# oled_iic.net
KiCad netlist of a schematic drawn in Altium Designer
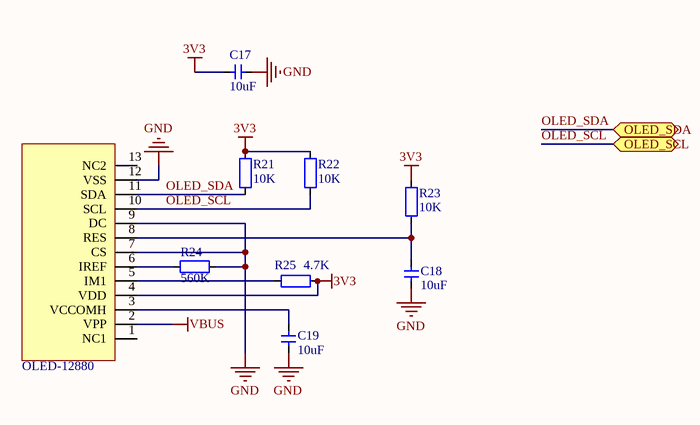
[diagram p0: oled_iic.SchDoc]

(export (version "E")
  (design (tool "Eeschema 10.0.6"))
  (components
    (comp (ref "1")
      (value "OLED-12880")
      (footprint "OLED-12880")
      (libsource (lib "mLib") (part "OLED-12880"))
    )
    (comp (ref "C17")
      (value "10uF")
      (footprint "CAP_0402")
      (description "Capacitor")
      (libsource (lib "MyPcbLib") (part "电容-0402"))
    )
    (comp (ref "C18")
      (value "10uF")
      (footprint "CAP_0402")
      (description "Capacitor")
      (libsource (lib "MyPcbLib") (part "电容-0402"))
    )
    (comp (ref "C19")
      (value "10uF")
      (footprint "CAP_0402")
      (description "Capacitor")
      (libsource (lib "MyPcbLib") (part "电容-0402"))
    )
    (comp (ref "R21")
      (value "10K")
      (footprint "RES_0402")
      (description "Resistor")
      (libsource (lib "") (part "电阻-0402_1"))
    )
    (comp (ref "R22")
      (value "10K")
      (footprint "RES_0402")
      (description "Resistor")
      (libsource (lib "") (part "电阻-0402_1"))
    )
    (comp (ref "R23")
      (value "10K")
      (footprint "RES_0402")
      (description "Resistor")
      (libsource (lib "") (part "电阻-0402_1"))
    )
    (comp (ref "R24")
      (value "560K")
      (footprint "RES_0402")
      (description "Resistor")
      (libsource (lib "MyPcbLib") (part "电阻-0402"))
    )
    (comp (ref "R25")
      (value "4.7K")
      (footprint "RES_0402")
      (description "Resistor")
      (libsource (lib "MyPcbLib") (part "电阻-0402"))
    )
  )
  (nets
    (net (code "1") (name "/OLED_SCL") (class "Default")
      (node (ref "1") (pin "10") (pinfunction "SCL_10") (pintype "passive"))
      (node (ref "R22") (pin "1") (pinfunction "1_1") (pintype "passive"))
    )
    (net (code "2") (name "/OLED_SDA") (class "Default")
      (node (ref "1") (pin "11") (pinfunction "SDA_11") (pintype "passive"))
      (node (ref "R21") (pin "1") (pinfunction "1_1") (pintype "passive"))
    )
    (net (code "3") (name "3V3") (class "Default")
      (node (ref "1") (pin "4") (pinfunction "VDD_4") (pintype "passive"))
      (node (ref "C17") (pin "2") (pinfunction "2_2") (pintype "passive"))
      (node (ref "R21") (pin "2") (pinfunction "2_2") (pintype "passive"))
      (node (ref "R22") (pin "2") (pinfunction "2_2") (pintype "passive"))
      (node (ref "R23") (pin "2") (pinfunction "2_2") (pintype "passive"))
      (node (ref "R25") (pin "2") (pinfunction "2_2") (pintype "passive"))
    )
    (net (code "4") (name "GND") (class "Default")
      (node (ref "1") (pin "12") (pinfunction "VSS_12") (pintype "passive"))
      (node (ref "1") (pin "7") (pinfunction "CS_7") (pintype "passive"))
      (node (ref "1") (pin "9") (pinfunction "DC_9") (pintype "passive"))
      (node (ref "C17") (pin "1") (pinfunction "1_1") (pintype "passive"))
      (node (ref "C18") (pin "1") (pinfunction "1_1") (pintype "passive"))
      (node (ref "C19") (pin "1") (pinfunction "1_1") (pintype "passive"))
      (node (ref "R24") (pin "2") (pinfunction "2_2") (pintype "passive"))
    )
    (net (code "5") (name "Net-(1-IM1)") (class "Default")
      (node (ref "1") (pin "5") (pinfunction "IM1_5") (pintype "passive"))
      (node (ref "R25") (pin "1") (pinfunction "1_1") (pintype "passive"))
    )
    (net (code "6") (name "Net-(1-IREF)") (class "Default")
      (node (ref "1") (pin "6") (pinfunction "IREF_6") (pintype "passive"))
      (node (ref "R24") (pin "1") (pinfunction "1_1") (pintype "passive"))
    )
    (net (code "7") (name "Net-(1-RES)") (class "Default")
      (node (ref "1") (pin "8") (pinfunction "RES_8") (pintype "passive"))
      (node (ref "C18") (pin "2") (pinfunction "2_2") (pintype "passive"))
      (node (ref "R23") (pin "1") (pinfunction "1_1") (pintype "passive"))
    )
    (net (code "8") (name "Net-(1-VCCOMH)") (class "Default")
      (node (ref "1") (pin "3") (pinfunction "VCCOMH_3") (pintype "passive"))
      (node (ref "C19") (pin "2") (pinfunction "2_2") (pintype "passive"))
    )
    (net (code "9") (name "VBUS") (class "Default")
      (node (ref "1") (pin "2") (pinfunction "VPP_2") (pintype "passive"))
    )
    (net (code "10") (name "unconnected-(1-NC1-Pad1)") (class "Default")
      (node (ref "1") (pin "1") (pinfunction "NC1_1") (pintype "passive"))
    )
    (net (code "11") (name "unconnected-(1-NC2-Pad13)") (class "Default")
      (node (ref "1") (pin "13") (pinfunction "NC2_13") (pintype "passive"))
    )
  )
)
